# Archimedes_Surucu_Kati.net
KiCad netlist of a schematic drawn in Altium Designer
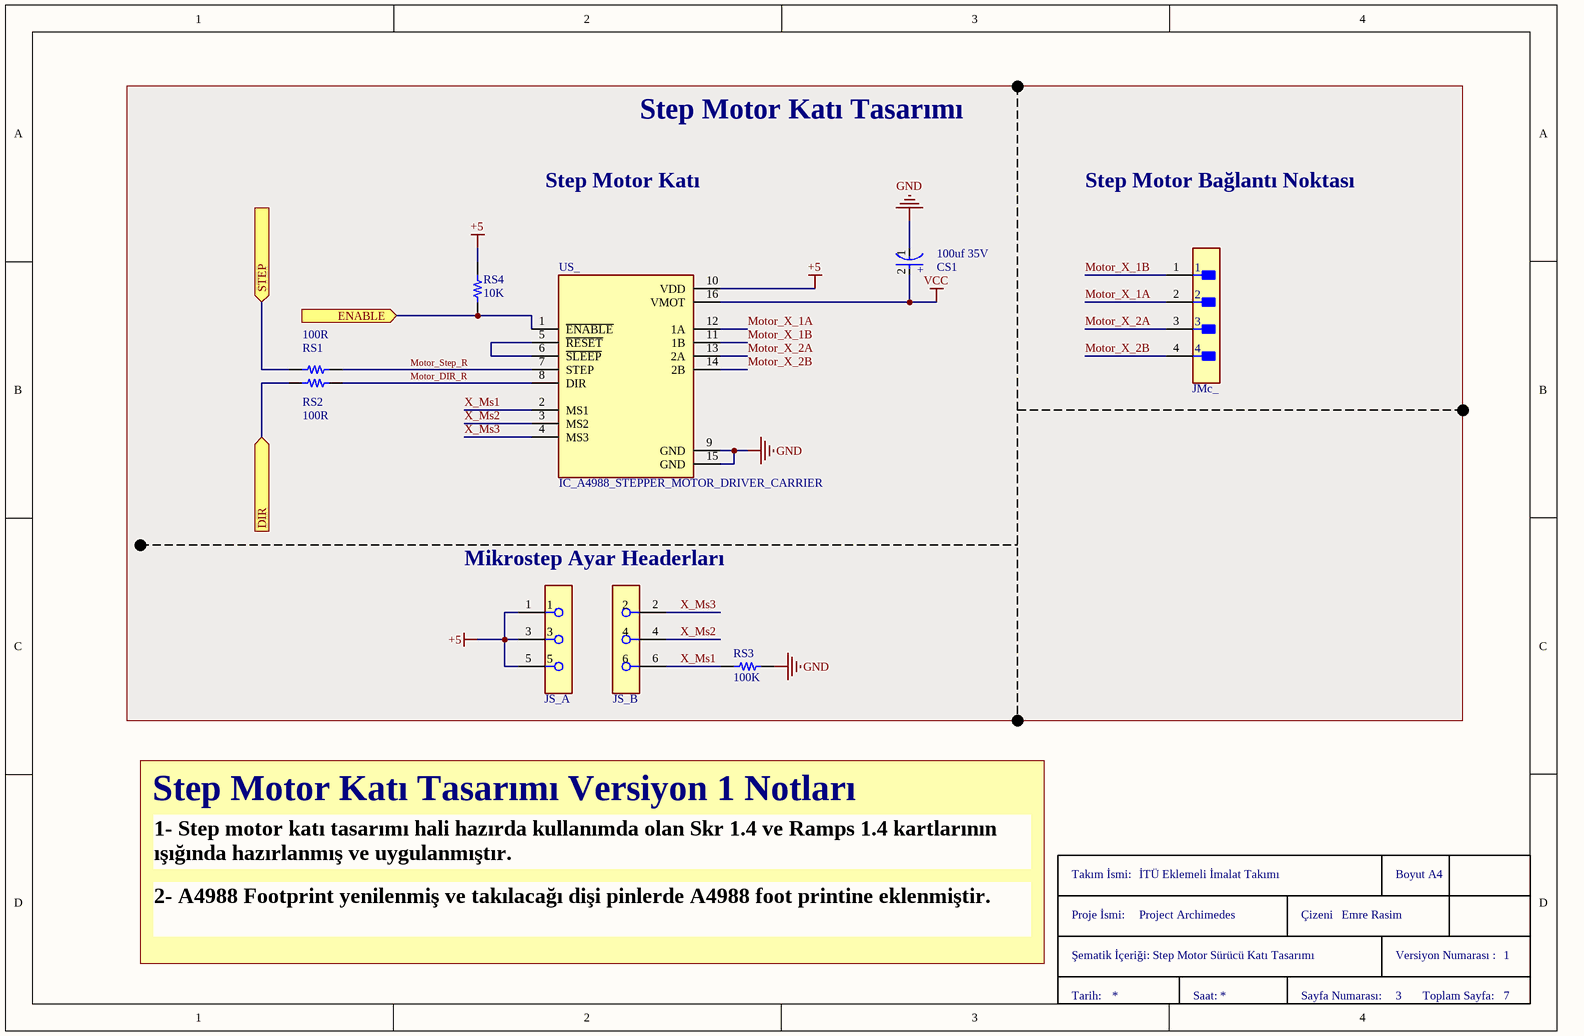
[diagram p0: Archimedes_Surucu_Kati.SchDoc]

(export (version "E")
  (design (tool "Eeschema 10.0.6"))
  (components
    (comp (ref "CS1")
      (value "100uf 35V")
      (footprint "C_Smd_D6.3_H_7.7_Electrolytic_Cap")
      (description "electrolytic capacitor with 100 uf and 35 volt rating")
      (libsource (lib "EKIM_Team_Main") (part "C_smd_D6.3_H7.7"))
    )
    (comp (ref "JMc_")
      (value "2.5 mm locked")
      (footprint "CON_2.5MM_4_LEAD_180_LOCKED")
      (description "2.5 mm 4 lead locked connector")
      (libsource (lib "EKIM_Team_Main") (part "Con_2.5mm_4_lead_180_locked"))
    )
    (comp (ref "JS_")
      (value "Con_3*2_Male_Header")
      (footprint "Con_3*2_Male_header")
      (description "3*2 male header")
      (libsource (lib "Buck") (part "Con_3*2_Male_Header"))
    )
    (comp (ref "RS1")
      (value "100R")
      (footprint "RES 0805/2012")
      (description "100 R ohm Resistor  with 805 pack and %1 tolerance rating")
      (libsource (lib "Pasifler") (part "Resistor 805"))
    )
    (comp (ref "RS2")
      (value "100R")
      (footprint "RES 0805/2012")
      (description "100 R ohm Resistor  with 805 pack and %1 tolerance rating")
      (libsource (lib "Pasifler") (part "Resistor 805"))
    )
    (comp (ref "RS3")
      (value "100K")
      (footprint "RES 0805/2012")
      (description "100 K ohm Resistor  with 805 pack and %1 tolerance rating")
      (libsource (lib "Pasifler") (part "Resistor 805"))
    )
    (comp (ref "RS4")
      (value "10K")
      (footprint "RES 0805/2012")
      (description "10 K ohm Resistor  with 805 pack and %1 tolerance rating")
      (libsource (lib "Pasifler") (part "Resistor 805"))
    )
    (comp (ref "TitleBlock-A4")
      (value "TitleBlock-A4")
      (description "Title Block for İTU eklemeli imalat takımı")
      (libsource (lib "EKIM_Team_Main") (part "TitleBlock-A4"))
    )
    (comp (ref "US_")
      (value "IC_A4988_STEPPER_MOTOR_DRIVER_CARRIER")
      (footprint "IC_A4988_STEPPER_MOTOR_DRIVER_CARRIER")
      (description "Stepper motor controler; IC: A4988; 1A; Uin mot: 8Ã·35V")
      (fields (field (name "MP") "A4988_STEPPER_MOTOR_DRIVER_CARRIER"))
      (libsource (lib "Buck") (part "IC_A4988_STEPPER_MOTOR_DRIVER_CARRIER"))
    )
  )
  (nets
    (net (code "1") (name "+5") (class "Default")
      (node (ref "JS_") (pin "1") (pinfunction "1_1") (pintype "passive"))
      (node (ref "JS_") (pin "3") (pinfunction "3_3") (pintype "passive"))
      (node (ref "JS_") (pin "5") (pinfunction "5_5") (pintype "passive"))
      (node (ref "RS4") (pin "2") (pinfunction "2_2") (pintype "passive"))
      (node (ref "US_") (pin "10") (pinfunction "VDD_10") (pintype "passive"))
    )
    (net (code "2") (name "/DIR") (class "Default")
      (node (ref "RS2") (pin "1") (pinfunction "1_1") (pintype "passive"))
    )
    (net (code "3") (name "/ENABLE") (class "Default")
      (node (ref "RS4") (pin "1") (pinfunction "1_1") (pintype "passive"))
      (node (ref "US_") (pin "1") (pinfunction "~{ENABLE}_1") (pintype "passive"))
    )
    (net (code "4") (name "/Motor_DIR_R") (class "Default")
      (node (ref "RS2") (pin "2") (pinfunction "2_2") (pintype "passive"))
      (node (ref "US_") (pin "8") (pinfunction "DIR_8") (pintype "passive"))
    )
    (net (code "5") (name "/Motor_Step_R") (class "Default")
      (node (ref "RS1") (pin "2") (pinfunction "2_2") (pintype "passive"))
      (node (ref "US_") (pin "7") (pinfunction "STEP_7") (pintype "passive"))
    )
    (net (code "6") (name "/Motor_X_1A") (class "Default")
      (node (ref "JMc_") (pin "2") (pinfunction "2_2") (pintype "passive"))
      (node (ref "US_") (pin "12") (pinfunction "1A_12") (pintype "passive"))
    )
    (net (code "7") (name "/Motor_X_1B") (class "Default")
      (node (ref "JMc_") (pin "1") (pinfunction "1_1") (pintype "passive"))
      (node (ref "US_") (pin "11") (pinfunction "1B_11") (pintype "passive"))
    )
    (net (code "8") (name "/Motor_X_2A") (class "Default")
      (node (ref "JMc_") (pin "3") (pinfunction "3_3") (pintype "passive"))
      (node (ref "US_") (pin "13") (pinfunction "2A_13") (pintype "passive"))
    )
    (net (code "9") (name "/Motor_X_2B") (class "Default")
      (node (ref "JMc_") (pin "4") (pinfunction "4_4") (pintype "passive"))
      (node (ref "US_") (pin "14") (pinfunction "2B_14") (pintype "passive"))
    )
    (net (code "10") (name "/STEP") (class "Default")
      (node (ref "RS1") (pin "1") (pinfunction "1_1") (pintype "passive"))
    )
    (net (code "11") (name "/X_Ms1") (class "Default")
      (node (ref "JS_") (pin "6") (pinfunction "6_6") (pintype "passive"))
      (node (ref "RS3") (pin "1") (pinfunction "1_1") (pintype "passive"))
      (node (ref "US_") (pin "2") (pinfunction "MS1_2") (pintype "passive"))
    )
    (net (code "12") (name "/X_Ms2") (class "Default")
      (node (ref "JS_") (pin "4") (pinfunction "4_4") (pintype "passive"))
      (node (ref "US_") (pin "3") (pinfunction "MS2_3") (pintype "passive"))
    )
    (net (code "13") (name "/X_Ms3") (class "Default")
      (node (ref "JS_") (pin "2") (pinfunction "2_2") (pintype "passive"))
      (node (ref "US_") (pin "4") (pinfunction "MS3_4") (pintype "passive"))
    )
    (net (code "14") (name "GND") (class "Default")
      (node (ref "CS1") (pin "1") (pinfunction "C_1") (pintype "passive"))
      (node (ref "RS3") (pin "2") (pinfunction "2_2") (pintype "passive"))
      (node (ref "US_") (pin "15") (pinfunction "GND_15") (pintype "power_in"))
      (node (ref "US_") (pin "9") (pinfunction "GND_9") (pintype "power_in"))
    )
    (net (code "15") (name "Net-(US_-~{RESET})") (class "Default")
      (node (ref "US_") (pin "5") (pinfunction "~{RESET}_5") (pintype "passive"))
      (node (ref "US_") (pin "6") (pinfunction "~{SLEEP}_6") (pintype "passive"))
    )
    (net (code "16") (name "VCC") (class "Default")
      (node (ref "CS1") (pin "2") (pinfunction "A_2") (pintype "passive"))
      (node (ref "US_") (pin "16") (pinfunction "VMOT_16") (pintype "passive"))
    )
  )
)
